# iMacG5-v2.net
KiCad netlist of a schematic drawn in EAGLE
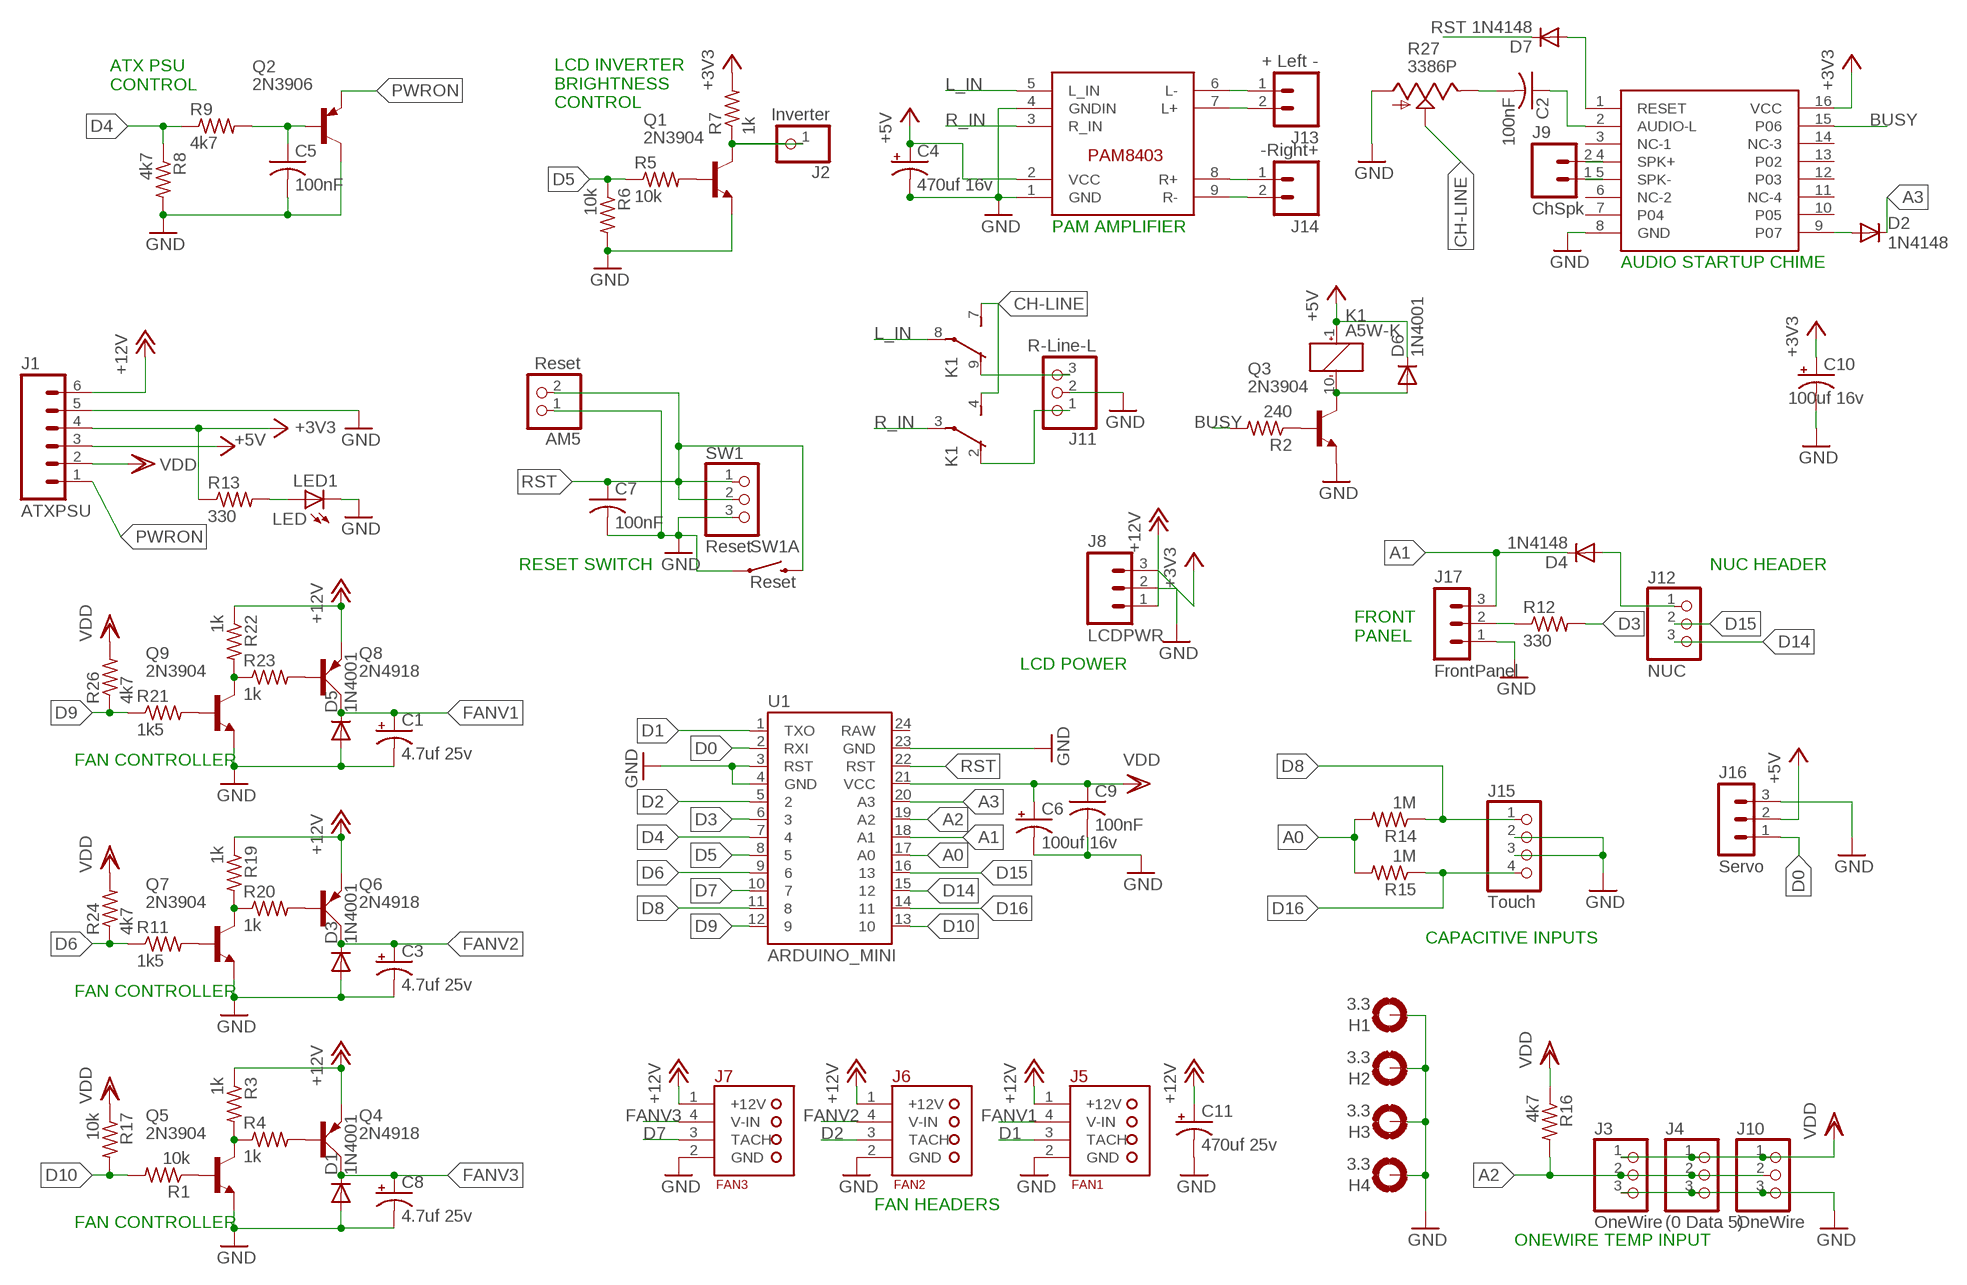
[diagram p0: schematic, sheet 1]

(export (version "E")
  (design (tool "Eeschema 10.0.6"))
  (components
    (comp (ref "AM5")
      (value "Reset")
      (footprint "eagle-import:1X02")
      (libsource (lib "eagle-import") (part "PINHD-1X2"))
    )
    (comp (ref "C1")
      (value "4.7uf 25v")
      (footprint "eagle-import:E2,5-5")
      (libsource (lib "eagle-import") (part "CPOL-USE2.5-5"))
    )
    (comp (ref "C2")
      (value "100nF")
      (footprint "eagle-import:C050-024X044")
      (libsource (lib "eagle-import") (part "C-US050-024X044"))
    )
    (comp (ref "C3")
      (value "4.7uf 25v")
      (footprint "eagle-import:E2,5-5")
      (libsource (lib "eagle-import") (part "CPOL-USE2.5-5"))
    )
    (comp (ref "C4")
      (value "470uf 16v")
      (footprint "eagle-import:E3,5-8")
      (libsource (lib "eagle-import") (part "CPOL-USE3.5-8"))
    )
    (comp (ref "C5")
      (value "100nF")
      (footprint "eagle-import:C050-024X044")
      (libsource (lib "eagle-import") (part "C-US050-024X044"))
    )
    (comp (ref "C6")
      (value "100uf 16v")
      (footprint "eagle-import:E2,5-5")
      (libsource (lib "eagle-import") (part "CPOL-USE2.5-5"))
    )
    (comp (ref "C7")
      (value "100nF")
      (footprint "eagle-import:C050-024X044")
      (libsource (lib "eagle-import") (part "C-US050-024X044"))
    )
    (comp (ref "C8")
      (value "4.7uf 25v")
      (footprint "eagle-import:E2,5-5")
      (libsource (lib "eagle-import") (part "CPOL-USE2.5-5"))
    )
    (comp (ref "C9")
      (value "100nF")
      (footprint "eagle-import:C050-024X044")
      (libsource (lib "eagle-import") (part "C-US050-024X044"))
    )
    (comp (ref "C10")
      (value "100uf 16v")
      (footprint "eagle-import:E2,5-5")
      (libsource (lib "eagle-import") (part "CPOL-USE2.5-5"))
    )
    (comp (ref "C11")
      (value "470uf 25v")
      (footprint "eagle-import:E3,5-8")
      (libsource (lib "eagle-import") (part "CPOL-USE3.5-8"))
    )
    (comp (ref "D1")
      (value "1N4001")
      (footprint "eagle-import:D-2.5")
      (libsource (lib "eagle-import") (part "DIODE-D-2.5"))
    )
    (comp (ref "D2")
      (value "1N4148")
      (footprint "eagle-import:D-2.5")
      (libsource (lib "eagle-import") (part "DIODE-D-2.5"))
    )
    (comp (ref "D3")
      (value "1N4001")
      (footprint "eagle-import:D-2.5")
      (libsource (lib "eagle-import") (part "DIODE-D-2.5"))
    )
    (comp (ref "D4")
      (value "1N4148")
      (footprint "eagle-import:D-2.5")
      (libsource (lib "eagle-import") (part "DIODE-D-2.5"))
    )
    (comp (ref "D5")
      (value "1N4001")
      (footprint "eagle-import:D-2.5")
      (libsource (lib "eagle-import") (part "DIODE-D-2.5"))
    )
    (comp (ref "D6")
      (value "1N4001")
      (footprint "eagle-import:D-7.5")
      (libsource (lib "eagle-import") (part "DIODE-D-7.5"))
    )
    (comp (ref "D7")
      (value "1N4148")
      (footprint "eagle-import:DO35-7")
      (libsource (lib "eagle-import") (part "1N4148DO35-7"))
    )
    (comp (ref "H1")
      (value "3.3")
      (footprint "eagle-import:3,3-PAD")
      (libsource (lib "eagle-import") (part "MOUNT-PAD-ROUND3.3"))
    )
    (comp (ref "H2")
      (value "3.3")
      (footprint "eagle-import:3,3-PAD")
      (libsource (lib "eagle-import") (part "MOUNT-PAD-ROUND3.3"))
    )
    (comp (ref "H3")
      (value "3.3")
      (footprint "eagle-import:3,3-PAD")
      (libsource (lib "eagle-import") (part "MOUNT-PAD-ROUND3.3"))
    )
    (comp (ref "H4")
      (value "3.3")
      (footprint "eagle-import:3,3-PAD")
      (libsource (lib "eagle-import") (part "MOUNT-PAD-ROUND3.3"))
    )
    (comp (ref "J1")
      (value "ATXPSU")
      (footprint "eagle-import:MOLEX-1X6")
      (libsource (lib "eagle-import") (part "M06POLAR"))
    )
    (comp (ref "J2")
      (value "Inverter")
      (footprint "eagle-import:1X01")
      (libsource (lib "eagle-import") (part "PINHD-1X1"))
    )
    (comp (ref "J3")
      (value "OneWire")
      (footprint "eagle-import:1X03")
      (libsource (lib "eagle-import") (part "PINHD-1X3"))
    )
    (comp (ref "J4")
      (value "(0 Data 5)")
      (footprint "eagle-import:1X03")
      (libsource (lib "eagle-import") (part "PINHD-1X3"))
    )
    (comp (ref "J5")
      (value "FAN1")
      (footprint "eagle-import:MOLEX-1X4")
      (libsource (lib "eagle-import") (part "IMAC-G5-FAN-2X3IMAC_G5_1X4"))
    )
    (comp (ref "J6")
      (value "FAN2")
      (footprint "eagle-import:IMAC_G5_2X3")
      (libsource (lib "eagle-import") (part "IMAC-G5-FAN-2X3"))
    )
    (comp (ref "J7")
      (value "FAN3")
      (footprint "eagle-import:IMAC_G5_2X3")
      (libsource (lib "eagle-import") (part "IMAC-G5-FAN-2X3"))
    )
    (comp (ref "J8")
      (value "LCDPWR")
      (footprint "eagle-import:MOLEX-1X3")
      (libsource (lib "eagle-import") (part "M03POLAR"))
    )
    (comp (ref "J9")
      (value "ChSpk")
      (footprint "eagle-import:MOLEX-1X2")
      (libsource (lib "eagle-import") (part "M02POLAR"))
    )
    (comp (ref "J10")
      (value "OneWire")
      (footprint "eagle-import:1X03")
      (libsource (lib "eagle-import") (part "PINHD-1X3"))
    )
    (comp (ref "J11")
      (value "R-Line-L")
      (footprint "eagle-import:1X03")
      (libsource (lib "eagle-import") (part "PINHD-1X3"))
    )
    (comp (ref "J12")
      (value "NUC")
      (footprint "eagle-import:1X03")
      (libsource (lib "eagle-import") (part "PINHD-1X3"))
    )
    (comp (ref "J13")
      (value "+ Left -")
      (footprint "eagle-import:MOLEX-1X2")
      (libsource (lib "eagle-import") (part "M02POLAR"))
    )
    (comp (ref "J14")
      (value "-Right+")
      (footprint "eagle-import:MOLEX-1X2")
      (libsource (lib "eagle-import") (part "M02POLAR"))
    )
    (comp (ref "J15")
      (value "Touch")
      (footprint "eagle-import:1X04")
      (libsource (lib "eagle-import") (part "PINHD-1X4"))
    )
    (comp (ref "J16")
      (value "Servo")
      (footprint "eagle-import:MA03-1")
      (libsource (lib "eagle-import") (part "MA03-1"))
    )
    (comp (ref "J17")
      (value "FrontPanel")
      (footprint "eagle-import:MA03-1")
      (libsource (lib "eagle-import") (part "MA03-1"))
    )
    (comp (ref "K1")
      (value "A5W-K")
      (footprint "eagle-import:TQ2")
      (fields (field (name "MF") "AROMAT/ MATSUSHITA") (field (name "MPN") "TQ2-5V"))
      (libsource (lib "eagle-import") (part "TQ2?-5V"))
    )
    (comp (ref "LED1")
      (value "LED")
      (footprint "eagle-import:LED3MM")
      (libsource (lib "eagle-import") (part "LED3MM"))
    )
    (comp (ref "Q1")
      (value "2N3904")
      (footprint "eagle-import:TO92")
      (libsource (lib "eagle-import") (part "2N3904"))
    )
    (comp (ref "Q2")
      (value "2N3906")
      (footprint "eagle-import:TO92")
      (libsource (lib "eagle-import") (part "2N3906"))
    )
    (comp (ref "Q3")
      (value "2N3904")
      (footprint "eagle-import:TO92")
      (libsource (lib "eagle-import") (part "2N3904"))
    )
    (comp (ref "Q4")
      (value "2N4918")
      (footprint "eagle-import:TO126AV")
      (libsource (lib "eagle-import") (part "BD438"))
    )
    (comp (ref "Q5")
      (value "2N3904")
      (footprint "eagle-import:TO92")
      (libsource (lib "eagle-import") (part "2N3904"))
    )
    (comp (ref "Q6")
      (value "2N4918")
      (footprint "eagle-import:TO126AV")
      (libsource (lib "eagle-import") (part "BD438"))
    )
    (comp (ref "Q7")
      (value "2N3904")
      (footprint "eagle-import:TO92")
      (libsource (lib "eagle-import") (part "2N3904"))
    )
    (comp (ref "Q8")
      (value "2N4918")
      (footprint "eagle-import:TO126AV")
      (libsource (lib "eagle-import") (part "BD438"))
    )
    (comp (ref "Q9")
      (value "2N3904")
      (footprint "eagle-import:TO92")
      (libsource (lib "eagle-import") (part "2N3904"))
    )
    (comp (ref "R1")
      (value "10k")
      (footprint "eagle-import:0207_7")
      (libsource (lib "eagle-import") (part "R-US_0207/7"))
    )
    (comp (ref "R2")
      (value "240")
      (footprint "eagle-import:0207_2V")
      (libsource (lib "eagle-import") (part "resistor_R-US_0207/2V"))
    )
    (comp (ref "R3")
      (value "1k")
      (footprint "eagle-import:0207_2V")
      (libsource (lib "eagle-import") (part "resistor_R-US_0207/2V"))
    )
    (comp (ref "R4")
      (value "1k")
      (footprint "eagle-import:0207_2V")
      (libsource (lib "eagle-import") (part "resistor_R-US_0207/2V"))
    )
    (comp (ref "R5")
      (value "10k")
      (footprint "eagle-import:0207_2V")
      (libsource (lib "eagle-import") (part "resistor_R-US_0207/2V"))
    )
    (comp (ref "R6")
      (value "10k")
      (footprint "eagle-import:0207_2V")
      (libsource (lib "eagle-import") (part "resistor_R-US_0207/2V"))
    )
    (comp (ref "R7")
      (value "1k")
      (footprint "eagle-import:0207_2V")
      (libsource (lib "eagle-import") (part "resistor_R-US_0207/2V"))
    )
    (comp (ref "R8")
      (value "4k7")
      (footprint "eagle-import:0207_2V")
      (libsource (lib "eagle-import") (part "resistor_R-US_0207/2V"))
    )
    (comp (ref "R9")
      (value "4k7")
      (footprint "eagle-import:0207_2V")
      (libsource (lib "eagle-import") (part "resistor_R-US_0207/2V"))
    )
    (comp (ref "R11")
      (value "1k5")
      (footprint "eagle-import:0207_2V")
      (libsource (lib "eagle-import") (part "resistor_R-US_0207/2V"))
    )
    (comp (ref "R12")
      (value "330")
      (footprint "eagle-import:0207_2V")
      (libsource (lib "eagle-import") (part "resistor_R-US_0207/2V"))
    )
    (comp (ref "R13")
      (value "330")
      (footprint "eagle-import:0207_2V")
      (libsource (lib "eagle-import") (part "resistor_R-US_0207/2V"))
    )
    (comp (ref "R14")
      (value "1M")
      (footprint "eagle-import:0207_7")
      (libsource (lib "eagle-import") (part "R-US_0207/7"))
    )
    (comp (ref "R15")
      (value "1M")
      (footprint "eagle-import:0207_7")
      (libsource (lib "eagle-import") (part "R-US_0207/7"))
    )
    (comp (ref "R16")
      (value "4k7")
      (footprint "eagle-import:0207_7")
      (libsource (lib "eagle-import") (part "R-US_0207/7"))
    )
    (comp (ref "R17")
      (value "10k")
      (footprint "eagle-import:0207_7")
      (libsource (lib "eagle-import") (part "R-US_0207/7"))
    )
    (comp (ref "R19")
      (value "1k")
      (footprint "eagle-import:0207_2V")
      (libsource (lib "eagle-import") (part "resistor_R-US_0207/2V"))
    )
    (comp (ref "R20")
      (value "1k")
      (footprint "eagle-import:0207_2V")
      (libsource (lib "eagle-import") (part "resistor_R-US_0207/2V"))
    )
    (comp (ref "R21")
      (value "1k5")
      (footprint "eagle-import:0207_2V")
      (libsource (lib "eagle-import") (part "resistor_R-US_0207/2V"))
    )
    (comp (ref "R22")
      (value "1k")
      (footprint "eagle-import:0207_2V")
      (libsource (lib "eagle-import") (part "resistor_R-US_0207/2V"))
    )
    (comp (ref "R23")
      (value "1k")
      (footprint "eagle-import:0207_2V")
      (libsource (lib "eagle-import") (part "resistor_R-US_0207/2V"))
    )
    (comp (ref "R24")
      (value "4k7")
      (footprint "eagle-import:0207_2V")
      (libsource (lib "eagle-import") (part "resistor_R-US_0207/2V"))
    )
    (comp (ref "R26")
      (value "4k7")
      (footprint "eagle-import:0207_2V")
      (libsource (lib "eagle-import") (part "resistor_R-US_0207/2V"))
    )
    (comp (ref "R27")
      (value "3386P")
      (footprint "eagle-import:B25P")
      (libsource (lib "eagle-import") (part "TRIM_US-B25P"))
    )
    (comp (ref "SW1")
      (value "Reset")
      (footprint "eagle-import:1X03")
      (libsource (lib "eagle-import") (part "PINHD-1X3"))
    )
    (comp (ref "SW1A")
      (value "Reset")
      (footprint "eagle-import:TACTILE-PTH")
      (libsource (lib "eagle-import") (part "SWITCH-MOMENTARY-2PTH"))
    )
    (comp (ref "U1")
      (value "ARDUINO_MINI")
      (footprint "eagle-import:ARDUINO_MINI")
      (libsource (lib "eagle-import") (part "ARDUINO_MINI"))
    )
    (comp (ref "U2")
      (value "PAM8403")
      (footprint "eagle-import:PAM8403")
      (libsource (lib "eagle-import") (part "PAM8403"))
    )
    (comp (ref "U3")
      (value "WTV020-SD-16P")
      (footprint "eagle-import:WTV020-SD-16P")
      (libsource (lib "eagle-import") (part "WTV020-SD-16P"))
    )
  )
  (nets
    (net (code "1") (name "+3V3") (class "Default")
      (node (ref "C10") (pin "+") (pinfunction "+_+") (pintype "passive"))
      (node (ref "J1") (pin "4") (pinfunction "4_4") (pintype "passive"))
      (node (ref "J8") (pin "3") (pinfunction "3_3") (pintype "passive"))
      (node (ref "R13") (pin "1") (pinfunction "1_1") (pintype "passive"))
      (node (ref "R7") (pin "2") (pinfunction "2_2") (pintype "passive"))
      (node (ref "U3") (pin "16") (pinfunction "VCC_16") (pintype "bidirectional"))
    )
    (net (code "2") (name "+5V") (class "Default")
      (node (ref "C4") (pin "+") (pinfunction "+_+") (pintype "passive"))
      (node (ref "D6") (pin "C") (pinfunction "C_C") (pintype "passive"))
      (node (ref "J1") (pin "3") (pinfunction "3_3") (pintype "passive"))
      (node (ref "J16") (pin "2") (pinfunction "2_2") (pintype "passive"))
      (node (ref "K1") (pin "1") (pinfunction "+_1") (pintype "passive"))
      (node (ref "U2") (pin "2") (pinfunction "VCC_2") (pintype "bidirectional"))
    )
    (net (code "3") (name "+12V") (class "Default")
      (node (ref "C11") (pin "+") (pinfunction "+_+") (pintype "passive"))
      (node (ref "J1") (pin "6") (pinfunction "6_6") (pintype "passive"))
      (node (ref "J5") (pin "1") (pinfunction "+12V_1") (pintype "bidirectional"))
      (node (ref "J6") (pin "1") (pinfunction "+12V_1") (pintype "bidirectional"))
      (node (ref "J7") (pin "1") (pinfunction "+12V_1") (pintype "bidirectional"))
      (node (ref "J8") (pin "1") (pinfunction "1_1") (pintype "passive"))
      (node (ref "Q4") (pin "E") (pinfunction "E_E") (pintype "passive"))
      (node (ref "Q6") (pin "E") (pinfunction "E_E") (pintype "passive"))
      (node (ref "Q8") (pin "E") (pinfunction "E_E") (pintype "passive"))
      (node (ref "R19") (pin "1") (pinfunction "1_1") (pintype "passive"))
      (node (ref "R22") (pin "1") (pinfunction "1_1") (pintype "passive"))
      (node (ref "R3") (pin "1") (pinfunction "1_1") (pintype "passive"))
    )
    (net (code "4") (name "/BUSY") (class "Default")
      (node (ref "R2") (pin "2") (pinfunction "2_2") (pintype "passive"))
      (node (ref "U3") (pin "15") (pinfunction "P06_15") (pintype "bidirectional"))
    )
    (net (code "5") (name "/L_IN") (class "Default")
      (node (ref "K1") (pin "8") (pinfunction "P_8") (pintype "passive"))
      (node (ref "U2") (pin "5") (pinfunction "L_IN_5") (pintype "bidirectional"))
    )
    (net (code "6") (name "/R_IN") (class "Default")
      (node (ref "K1") (pin "3") (pinfunction "P_3") (pintype "passive"))
      (node (ref "U2") (pin "3") (pinfunction "R_IN_3") (pintype "bidirectional"))
    )
    (net (code "7") (name "A0") (class "Default")
      (node (ref "R14") (pin "2") (pinfunction "2_2") (pintype "passive"))
      (node (ref "R15") (pin "2") (pinfunction "2_2") (pintype "passive"))
      (node (ref "U1") (pin "17") (pinfunction "A0_17") (pintype "bidirectional"))
    )
    (net (code "8") (name "A1") (class "Default")
      (node (ref "D4") (pin "C") (pinfunction "C_C") (pintype "passive"))
      (node (ref "J17") (pin "3") (pinfunction "3_3") (pintype "passive"))
      (node (ref "U1") (pin "18") (pinfunction "A1_18") (pintype "bidirectional"))
    )
    (net (code "9") (name "A2") (class "Default")
      (node (ref "J10") (pin "2") (pinfunction "2_2") (pintype "passive"))
      (node (ref "J3") (pin "2") (pinfunction "2_2") (pintype "passive"))
      (node (ref "J4") (pin "2") (pinfunction "2_2") (pintype "passive"))
      (node (ref "R16") (pin "2") (pinfunction "2_2") (pintype "passive"))
      (node (ref "U1") (pin "19") (pinfunction "A2_19") (pintype "bidirectional"))
    )
    (net (code "10") (name "A3") (class "Default")
      (node (ref "D2") (pin "C") (pinfunction "C_C") (pintype "passive"))
      (node (ref "U1") (pin "20") (pinfunction "A3_20") (pintype "bidirectional"))
    )
    (net (code "11") (name "CH-LINE") (class "Default")
      (node (ref "K1") (pin "4") (pinfunction "S_4") (pintype "passive"))
      (node (ref "K1") (pin "7") (pinfunction "S_7") (pintype "passive"))
      (node (ref "R27") (pin "S") (pinfunction "S_S") (pintype "passive"))
    )
    (net (code "12") (name "D0") (class "Default")
      (node (ref "J16") (pin "1") (pinfunction "1_1") (pintype "passive"))
      (node (ref "U1") (pin "2") (pinfunction "RXI_2") (pintype "bidirectional"))
    )
    (net (code "13") (name "D1") (class "Default")
      (node (ref "J5") (pin "3") (pinfunction "TACH_3") (pintype "bidirectional"))
      (node (ref "U1") (pin "1") (pinfunction "TXO_1") (pintype "bidirectional"))
    )
    (net (code "14") (name "D2") (class "Default")
      (node (ref "J6") (pin "3") (pinfunction "TACH_3") (pintype "bidirectional"))
      (node (ref "U1") (pin "5") (pinfunction "2_5") (pintype "bidirectional"))
    )
    (net (code "15") (name "D3") (class "Default")
      (node (ref "R12") (pin "2") (pinfunction "2_2") (pintype "passive"))
      (node (ref "U1") (pin "6") (pinfunction "3_6") (pintype "bidirectional"))
    )
    (net (code "16") (name "D4") (class "Default")
      (node (ref "R8") (pin "1") (pinfunction "1_1") (pintype "passive"))
      (node (ref "R9") (pin "1") (pinfunction "1_1") (pintype "passive"))
      (node (ref "U1") (pin "7") (pinfunction "4_7") (pintype "bidirectional"))
    )
    (net (code "17") (name "D5") (class "Default")
      (node (ref "R5") (pin "1") (pinfunction "1_1") (pintype "passive"))
      (node (ref "R6") (pin "1") (pinfunction "1_1") (pintype "passive"))
      (node (ref "U1") (pin "8") (pinfunction "5_8") (pintype "bidirectional"))
    )
    (net (code "18") (name "D6") (class "Default")
      (node (ref "R11") (pin "1") (pinfunction "1_1") (pintype "passive"))
      (node (ref "R24") (pin "1") (pinfunction "1_1") (pintype "passive"))
      (node (ref "U1") (pin "9") (pinfunction "6_9") (pintype "bidirectional"))
    )
    (net (code "19") (name "D7") (class "Default")
      (node (ref "J7") (pin "3") (pinfunction "TACH_3") (pintype "bidirectional"))
      (node (ref "U1") (pin "10") (pinfunction "7_10") (pintype "bidirectional"))
    )
    (net (code "20") (name "D8") (class "Default")
      (node (ref "J15") (pin "1") (pinfunction "1_1") (pintype "passive"))
      (node (ref "R14") (pin "1") (pinfunction "1_1") (pintype "passive"))
      (node (ref "U1") (pin "11") (pinfunction "8_11") (pintype "bidirectional"))
    )
    (net (code "21") (name "D9") (class "Default")
      (node (ref "R21") (pin "1") (pinfunction "1_1") (pintype "passive"))
      (node (ref "R26") (pin "1") (pinfunction "1_1") (pintype "passive"))
      (node (ref "U1") (pin "12") (pinfunction "9_12") (pintype "bidirectional"))
    )
    (net (code "22") (name "D10") (class "Default")
      (node (ref "R1") (pin "2") (pinfunction "2_2") (pintype "passive"))
      (node (ref "R17") (pin "2") (pinfunction "2_2") (pintype "passive"))
      (node (ref "U1") (pin "13") (pinfunction "10_13") (pintype "bidirectional"))
    )
    (net (code "23") (name "D14") (class "Default")
      (node (ref "J12") (pin "3") (pinfunction "3_3") (pintype "passive"))
      (node (ref "U1") (pin "15") (pinfunction "12_15") (pintype "bidirectional"))
    )
    (net (code "24") (name "D15") (class "Default")
      (node (ref "J12") (pin "2") (pinfunction "2_2") (pintype "passive"))
      (node (ref "U1") (pin "16") (pinfunction "13_16") (pintype "bidirectional"))
    )
    (net (code "25") (name "D16") (class "Default")
      (node (ref "J15") (pin "4") (pinfunction "4_4") (pintype "passive"))
      (node (ref "R15") (pin "1") (pinfunction "1_1") (pintype "passive"))
      (node (ref "U1") (pin "14") (pinfunction "11_14") (pintype "bidirectional"))
    )
    (net (code "26") (name "FANV1") (class "Default")
      (node (ref "C1") (pin "+") (pinfunction "+_+") (pintype "passive"))
      (node (ref "D5") (pin "C") (pinfunction "C_C") (pintype "passive"))
      (node (ref "J5") (pin "4") (pinfunction "V-IN_4") (pintype "bidirectional"))
      (node (ref "Q8") (pin "C") (pinfunction "C_C") (pintype "passive"))
    )
    (net (code "27") (name "FANV2") (class "Default")
      (node (ref "C3") (pin "+") (pinfunction "+_+") (pintype "passive"))
      (node (ref "D3") (pin "C") (pinfunction "C_C") (pintype "passive"))
      (node (ref "J6") (pin "4") (pinfunction "V-IN_4") (pintype "bidirectional"))
      (node (ref "Q6") (pin "C") (pinfunction "C_C") (pintype "passive"))
    )
    (net (code "28") (name "FANV3") (class "Default")
      (node (ref "C8") (pin "+") (pinfunction "+_+") (pintype "passive"))
      (node (ref "D1") (pin "C") (pinfunction "C_C") (pintype "passive"))
      (node (ref "J7") (pin "4") (pinfunction "V-IN_4") (pintype "bidirectional"))
      (node (ref "Q4") (pin "C") (pinfunction "C_C") (pintype "passive"))
    )
    (net (code "29") (name "GND") (class "Default")
      (node (ref "AM5") (pin "1") (pinfunction "1_1") (pintype "passive"))
      (node (ref "C1") (pin "-") (pinfunction "-_-") (pintype "passive"))
      (node (ref "C10") (pin "-") (pinfunction "-_-") (pintype "passive"))
      (node (ref "C11") (pin "-") (pinfunction "-_-") (pintype "passive"))
      (node (ref "C3") (pin "-") (pinfunction "-_-") (pintype "passive"))
      (node (ref "C4") (pin "-") (pinfunction "-_-") (pintype "passive"))
      (node (ref "C5") (pin "2") (pinfunction "2_2") (pintype "passive"))
      (node (ref "C6") (pin "-") (pinfunction "-_-") (pintype "passive"))
      (node (ref "C7") (pin "2") (pinfunction "2_2") (pintype "passive"))
      (node (ref "C8") (pin "-") (pinfunction "-_-") (pintype "passive"))
      (node (ref "C9") (pin "2") (pinfunction "2_2") (pintype "passive"))
      (node (ref "D1") (pin "A") (pinfunction "A_A") (pintype "passive"))
      (node (ref "D3") (pin "A") (pinfunction "A_A") (pintype "passive"))
      (node (ref "D5") (pin "A") (pinfunction "A_A") (pintype "passive"))
      (node (ref "H1") (pin "B3,3") (pinfunction "MOUNT_B3,3") (pintype "passive"))
      (node (ref "H2") (pin "B3,3") (pinfunction "MOUNT_B3,3") (pintype "passive"))
      (node (ref "H3") (pin "B3,3") (pinfunction "MOUNT_B3,3") (pintype "passive"))
      (node (ref "H4") (pin "B3,3") (pinfunction "MOUNT_B3,3") (pintype "passive"))
      (node (ref "J1") (pin "5") (pinfunction "5_5") (pintype "passive"))
      (node (ref "J10") (pin "3") (pinfunction "3_3") (pintype "passive"))
      (node (ref "J11") (pin "2") (pinfunction "2_2") (pintype "passive"))
      (node (ref "J15") (pin "2") (pinfunction "2_2") (pintype "passive"))
      (node (ref "J15") (pin "3") (pinfunction "3_3") (pintype "passive"))
      (node (ref "J16") (pin "3") (pinfunction "3_3") (pintype "passive"))
      (node (ref "J17") (pin "1") (pinfunction "1_1") (pintype "passive"))
      (node (ref "J3") (pin "3") (pinfunction "3_3") (pintype "passive"))
      (node (ref "J4") (pin "3") (pinfunction "3_3") (pintype "passive"))
      (node (ref "J5") (pin "2") (pinfunction "GND_2") (pintype "bidirectional"))
      (node (ref "J6") (pin "2") (pinfunction "GND_2") (pintype "bidirectional"))
      (node (ref "J7") (pin "2") (pinfunction "GND_2") (pintype "bidirectional"))
      (node (ref "J8") (pin "2") (pinfunction "2_2") (pintype "passive"))
      (node (ref "LED1") (pin "K") (pinfunction "C_K") (pintype "passive"))
      (node (ref "Q1") (pin "3") (pinfunction "E_3") (pintype "passive"))
      (node (ref "Q2") (pin "1") (pinfunction "C_1") (pintype "passive"))
      (node (ref "Q3") (pin "3") (pinfunction "E_3") (pintype "passive"))
      (node (ref "Q5") (pin "3") (pinfunction "E_3") (pintype "passive"))
      (node (ref "Q7") (pin "3") (pinfunction "E_3") (pintype "passive"))
      (node (ref "Q9") (pin "3") (pinfunction "E_3") (pintype "passive"))
      (node (ref "R27") (pin "A") (pinfunction "A_A") (pintype "passive"))
      (node (ref "R6") (pin "2") (pinfunction "2_2") (pintype "passive"))
      (node (ref "R8") (pin "2") (pinfunction "2_2") (pintype "passive"))
      (node (ref "SW1") (pin "3") (pinfunction "3_3") (pintype "passive"))
      (node (ref "SW1A") (pin "1") (pinfunction "1_1") (pintype "passive"))
      (node (ref "U1") (pin "23") (pinfunction "GND_23") (pintype "bidirectional"))
      (node (ref "U1") (pin "3") (pinfunction "RST_3") (pintype "bidirectional"))
      (node (ref "U1") (pin "4") (pinfunction "GND_4") (pintype "bidirectional"))
      (node (ref "U2") (pin "1") (pinfunction "GND_1") (pintype "bidirectional"))
      (node (ref "U2") (pin "4") (pinfunction "GNDIN_4") (pintype "bidirectional"))
      (node (ref "U3") (pin "8") (pinfunction "GND_8") (pintype "bidirectional"))
    )
    (net (code "30") (name "Net-(C2-Pad2)") (class "Default")
      (node (ref "C2") (pin "2") (pinfunction "2_2") (pintype "passive"))
      (node (ref "R27") (pin "E") (pinfunction "E_E") (pintype "passive"))
    )
    (net (code "31") (name "Net-(D4-PadA)") (class "Default")
      (node (ref "D4") (pin "A") (pinfunction "A_A") (pintype "passive"))
      (node (ref "J12") (pin "1") (pinfunction "1_1") (pintype "passive"))
    )
    (net (code "32") (name "Net-(J17-Pad2)") (class "Default")
      (node (ref "J17") (pin "2") (pinfunction "2_2") (pintype "passive"))
      (node (ref "R12") (pin "1") (pinfunction "1_1") (pintype "passive"))
    )
    (net (code "33") (name "Net-(K1A-O)") (class "Default")
      (node (ref "J11") (pin "1") (pinfunction "1_1") (pintype "passive"))
      (node (ref "K1") (pin "2") (pinfunction "O_2") (pintype "passive"))
    )
    (net (code "34") (name "Net-(K1B-O)") (class "Default")
      (node (ref "J11") (pin "3") (pinfunction "3_3") (pintype "passive"))
      (node (ref "K1") (pin "9") (pinfunction "O_9") (pintype "passive"))
    )
    (net (code "35") (name "Net-(K1C--)") (class "Default")
      (node (ref "D6") (pin "A") (pinfunction "A_A") (pintype "passive"))
      (node (ref "K1") (pin "10") (pinfunction "-_10") (pintype "passive"))
      (node (ref "Q3") (pin "1") (pinfunction "C_1") (pintype "passive"))
    )
    (net (code "36") (name "Net-(LED1-PadA)") (class "Default")
      (node (ref "LED1") (pin "A") (pinfunction "A_A") (pintype "passive"))
      (node (ref "R13") (pin "2") (pinfunction "2_2") (pintype "passive"))
    )
    (net (code "37") (name "Net-(Q1-B)") (class "Default")
      (node (ref "Q1") (pin "2") (pinfunction "B_2") (pintype "passive"))
      (node (ref "R5") (pin "2") (pinfunction "2_2") (pintype "passive"))
    )
    (net (code "38") (name "Net-(Q1-C)") (class "Default")
      (node (ref "J2") (pin "1") (pinfunction "1_1") (pintype "passive"))
      (node (ref "Q1") (pin "1") (pinfunction "C_1") (pintype "passive"))
      (node (ref "R7") (pin "1") (pinfunction "1_1") (pintype "passive"))
    )
    (net (code "39") (name "Net-(Q2-B)") (class "Default")
      (node (ref "C5") (pin "1") (pinfunction "1_1") (pintype "passive"))
      (node (ref "Q2") (pin "2") (pinfunction "B_2") (pintype "passive"))
      (node (ref "R9") (pin "2") (pinfunction "2_2") (pintype "passive"))
    )
    (net (code "40") (name "Net-(Q3-B)") (class "Default")
      (node (ref "Q3") (pin "2") (pinfunction "B_2") (pintype "passive"))
      (node (ref "R2") (pin "1") (pinfunction "1_1") (pintype "passive"))
    )
    (net (code "41") (name "Net-(Q4-PadB)") (class "Default")
      (node (ref "Q4") (pin "B") (pinfunction "B_B") (pintype "passive"))
      (node (ref "R4") (pin "2") (pinfunction "2_2") (pintype "passive"))
    )
    (net (code "42") (name "Net-(Q5-B)") (class "Default")
      (node (ref "Q5") (pin "2") (pinfunction "B_2") (pintype "passive"))
      (node (ref "R1") (pin "1") (pinfunction "1_1") (pintype "passive"))
    )
    (net (code "43") (name "Net-(Q5-C)") (class "Default")
      (node (ref "Q5") (pin "1") (pinfunction "C_1") (pintype "passive"))
      (node (ref "R3") (pin "2") (pinfunction "2_2") (pintype "passive"))
      (node (ref "R4") (pin "1") (pinfunction "1_1") (pintype "passive"))
    )
    (net (code "44") (name "Net-(Q6-PadB)") (class "Default")
      (node (ref "Q6") (pin "B") (pinfunction "B_B") (pintype "passive"))
      (node (ref "R20") (pin "2") (pinfunction "2_2") (pintype "passive"))
    )
    (net (code "45") (name "Net-(Q7-B)") (class "Default")
      (node (ref "Q7") (pin "2") (pinfunction "B_2") (pintype "passive"))
      (node (ref "R11") (pin "2") (pinfunction "2_2") (pintype "passive"))
    )
    (net (code "46") (name "Net-(Q7-C)") (class "Default")
      (node (ref "Q7") (pin "1") (pinfunction "C_1") (pintype "passive"))
      (node (ref "R19") (pin "2") (pinfunction "2_2") (pintype "passive"))
      (node (ref "R20") (pin "1") (pinfunction "1_1") (pintype "passive"))
    )
    (net (code "47") (name "Net-(Q8-PadB)") (class "Default")
      (node (ref "Q8") (pin "B") (pinfunction "B_B") (pintype "passive"))
      (node (ref "R23") (pin "2") (pinfunction "2_2") (pintype "passive"))
    )
    (net (code "48") (name "Net-(Q9-B)") (class "Default")
      (node (ref "Q9") (pin "2") (pinfunction "B_2") (pintype "passive"))
      (node (ref "R21") (pin "2") (pinfunction "2_2") (pintype "passive"))
    )
    (net (code "49") (name "Net-(Q9-C)") (class "Default")
      (node (ref "Q9") (pin "1") (pinfunction "C_1") (pintype "passive"))
      (node (ref "R22") (pin "2") (pinfunction "2_2") (pintype "passive"))
      (node (ref "R23") (pin "1") (pinfunction "1_1") (pintype "passive"))
    )
    (net (code "50") (name "Net-(U2-L+)") (class "Default")
      (node (ref "J13") (pin "2") (pinfunction "2_2") (pintype "passive"))
      (node (ref "U2") (pin "7") (pinfunction "L+_7") (pintype "bidirectional"))
    )
    (net (code "51") (name "Net-(U2-L-)") (class "Default")
      (node (ref "J13") (pin "1") (pinfunction "1_1") (pintype "passive"))
      (node (ref "U2") (pin "6") (pinfunction "L-_6") (pintype "bidirectional"))
    )
    (net (code "52") (name "Net-(U2-R+)") (class "Default")
      (node (ref "J14") (pin "1") (pinfunction "1_1") (pintype "passive"))
      (node (ref "U2") (pin "8") (pinfunction "R+_8") (pintype "bidirectional"))
    )
    (net (code "53") (name "Net-(U2-R-)") (class "Default")
      (node (ref "J14") (pin "2") (pinfunction "2_2") (pintype "passive"))
      (node (ref "U2") (pin "9") (pinfunction "R-_9") (pintype "bidirectional"))
    )
    (net (code "54") (name "Net-(U3-AUDIO-L)") (class "Default")
      (node (ref "C2") (pin "1") (pinfunction "1_1") (pintype "passive"))
      (node (ref "U3") (pin "2") (pinfunction "AUDIO-L_2") (pintype "bidirectional"))
    )
    (net (code "55") (name "Net-(U3-P07)") (class "Default")
      (node (ref "D2") (pin "A") (pinfunction "A_A") (pintype "passive"))
      (node (ref "U3") (pin "9") (pinfunction "P07_9") (pintype "bidirectional"))
    )
    (net (code "56") (name "Net-(U3-RESET)") (class "Default")
      (node (ref "D7") (pin "A") (pinfunction "A_A") (pintype "passive"))
      (node (ref "U3") (pin "1") (pinfunction "RESET_1") (pintype "bidirectional"))
    )
    (net (code "57") (name "Net-(U3-SPK+)") (class "Default")
      (node (ref "J9") (pin "2") (pinfunction "2_2") (pintype "passive"))
      (node (ref "U3") (pin "4") (pinfunction "SPK+_4") (pintype "bidirectional"))
    )
    (net (code "58") (name "Net-(U3-SPK-)") (class "Default")
      (node (ref "J9") (pin "1") (pinfunction "1_1") (pintype "passive"))
      (node (ref "U3") (pin "5") (pinfunction "SPK-_5") (pintype "bidirectional"))
    )
    (net (code "59") (name "PWRON") (class "Default")
      (node (ref "J1") (pin "1") (pinfunction "1_1") (pintype "passive"))
      (node (ref "Q2") (pin "3") (pinfunction "E_3") (pintype "passive"))
    )
    (net (code "60") (name "RST") (class "Default")
      (node (ref "AM5") (pin "2") (pinfunction "2_2") (pintype "passive"))
      (node (ref "C7") (pin "1") (pinfunction "1_1") (pintype "passive"))
      (node (ref "D7") (pin "C") (pinfunction "C_C") (pintype "passive"))
      (node (ref "SW1") (pin "1") (pinfunction "1_1") (pintype "passive"))
      (node (ref "SW1") (pin "2") (pinfunction "2_2") (pintype "passive"))
      (node (ref "SW1A") (pin "3") (pinfunction "2_3") (pintype "passive"))
      (node (ref "U1") (pin "22") (pinfunction "RST_22") (pintype "bidirectional"))
    )
    (net (code "61") (name "VDD") (class "Default")
      (node (ref "C6") (pin "+") (pinfunction "+_+") (pintype "passive"))
      (node (ref "C9") (pin "1") (pinfunction "1_1") (pintype "passive"))
      (node (ref "J1") (pin "2") (pinfunction "2_2") (pintype "passive"))
      (node (ref "J10") (pin "1") (pinfunction "1_1") (pintype "passive"))
      (node (ref "J3") (pin "1") (pinfunction "1_1") (pintype "passive"))
      (node (ref "J4") (pin "1") (pinfunction "1_1") (pintype "passive"))
      (node (ref "R16") (pin "1") (pinfunction "1_1") (pintype "passive"))
      (node (ref "R17") (pin "1") (pinfunction "1_1") (pintype "passive"))
      (node (ref "R24") (pin "2") (pinfunction "2_2") (pintype "passive"))
      (node (ref "R26") (pin "2") (pinfunction "2_2") (pintype "passive"))
      (node (ref "U1") (pin "21") (pinfunction "VCC_21") (pintype "bidirectional"))
    )
    (net (code "62") (name "unconnected-(U1-RAW-Pad24)") (class "Default")
      (node (ref "U1") (pin "24") (pinfunction "RAW_24") (pintype "bidirectional"))
    )
    (net (code "63") (name "unconnected-(U3-NC-1-Pad3)") (class "Default")
      (node (ref "U3") (pin "3") (pinfunction "NC-1_3") (pintype "bidirectional"))
    )
    (net (code "64") (name "unconnected-(U3-NC-2-Pad6)") (class "Default")
      (node (ref "U3") (pin "6") (pinfunction "NC-2_6") (pintype "bidirectional"))
    )
    (net (code "65") (name "unconnected-(U3-NC-3-Pad14)") (class "Default")
      (node (ref "U3") (pin "14") (pinfunction "NC-3_14") (pintype "bidirectional"))
    )
    (net (code "66") (name "unconnected-(U3-NC-4-Pad11)") (class "Default")
      (node (ref "U3") (pin "11") (pinfunction "NC-4_11") (pintype "bidirectional"))
    )
    (net (code "67") (name "unconnected-(U3-P02-Pad13)") (class "Default")
      (node (ref "U3") (pin "13") (pinfunction "P02_13") (pintype "bidirectional"))
    )
    (net (code "68") (name "unconnected-(U3-P03-Pad12)") (class "Default")
      (node (ref "U3") (pin "12") (pinfunction "P03_12") (pintype "bidirectional"))
    )
    (net (code "69") (name "unconnected-(U3-P04-Pad7)") (class "Default")
      (node (ref "U3") (pin "7") (pinfunction "P04_7") (pintype "bidirectional"))
    )
    (net (code "70") (name "unconnected-(U3-P05-Pad10)") (class "Default")
      (node (ref "U3") (pin "10") (pinfunction "P05_10") (pintype "bidirectional"))
    )
  )
)
